# libre_oven_devkit.net
KiCad netlist of a schematic drawn in EasyEDA Pro
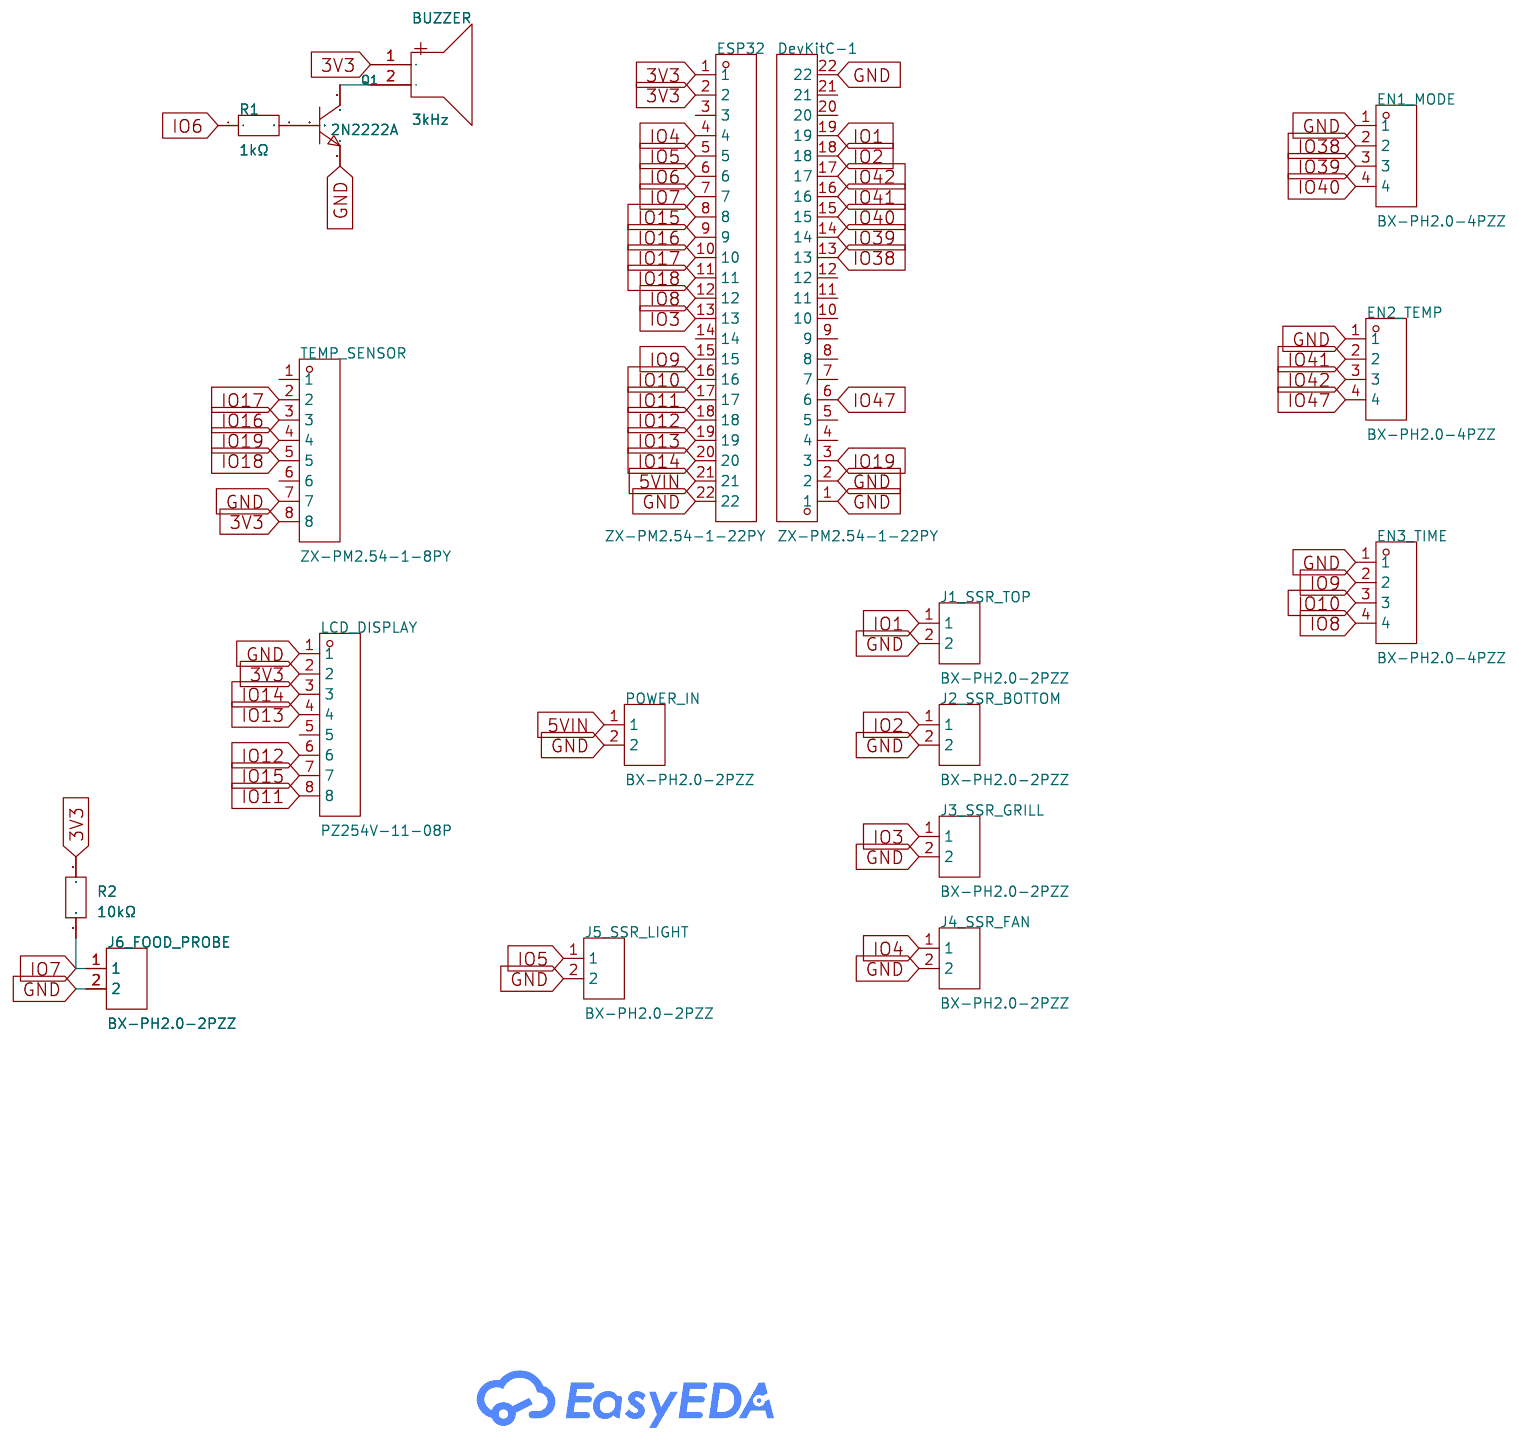
[diagram p0: schematic sheet]

(export (version "E")
  (design (tool "Eeschema 10.0.6"))
  (components
    (comp (ref "BUZZER")
      (value "3kHz")
      (footprint "easyedapro:BUZ-TH_BD9.0-P5.00-D0.6-FD")
      (fields (field (name "Manufacturer Part") "HNB09A03") (field (name "Manufacturer") "华能"))
      (libsource (lib "easyedapro") (part "HNB09A03"))
    )
    (comp (ref "DevKitC-1")
      (value "ZX-PM2.54-1-22PY")
      (footprint "easyedapro:HDR-TH_22P-P2.54-V-F")
      (fields (field (name "Manufacturer") "Megastar(兆星)"))
      (libsource (lib "easyedapro") (part "ZX-PM2.54-1-22PY"))
    )
    (comp (ref "EN1_MODE")
      (value "BX-PH2.0-4PZZ")
      (footprint "easyedapro:CONN-TH_4P-P2.00_BX-PH2.0-4PZZ")
      (fields (field (name "Manufacturer") "Bossie(博锡)"))
      (libsource (lib "easyedapro") (part "BX-PH2.0-4PZZ"))
    )
    (comp (ref "EN2_TEMP")
      (value "BX-PH2.0-4PZZ")
      (footprint "easyedapro:CONN-TH_4P-P2.00_BX-PH2.0-4PZZ")
      (fields (field (name "Manufacturer") "Bossie(博锡)"))
      (libsource (lib "easyedapro") (part "BX-PH2.0-4PZZ"))
    )
    (comp (ref "EN3_TIME")
      (value "BX-PH2.0-4PZZ")
      (footprint "easyedapro:CONN-TH_4P-P2.00_BX-PH2.0-4PZZ")
      (fields (field (name "Manufacturer") "Bossie(博锡)"))
      (libsource (lib "easyedapro") (part "BX-PH2.0-4PZZ"))
    )
    (comp (ref "ESP32")
      (value "ZX-PM2.54-1-22PY")
      (footprint "easyedapro:HDR-TH_22P-P2.54-V-F")
      (fields (field (name "Manufacturer") "Megastar(兆星)"))
      (libsource (lib "easyedapro") (part "ZX-PM2.54-1-22PY"))
    )
    (comp (ref "J1_SSR_TOP")
      (value "BX-PH2.0-2PZZ")
      (footprint "easyedapro:CONN-TH_2P-P2.00_BOSSIE_BX-PH2.0-2PZZ")
      (fields (field (name "Manufacturer") "Bossie(博锡)"))
      (libsource (lib "easyedapro") (part "BX-PH2.0-2PZZ"))
    )
    (comp (ref "J2_SSR_BOTTOM")
      (value "BX-PH2.0-2PZZ")
      (footprint "easyedapro:CONN-TH_2P-P2.00_BOSSIE_BX-PH2.0-2PZZ")
      (fields (field (name "Manufacturer") "Bossie(博锡)"))
      (libsource (lib "easyedapro") (part "BX-PH2.0-2PZZ"))
    )
    (comp (ref "J3_SSR_GRILL")
      (value "BX-PH2.0-2PZZ")
      (footprint "easyedapro:CONN-TH_2P-P2.00_BOSSIE_BX-PH2.0-2PZZ")
      (fields (field (name "Manufacturer") "Bossie(博锡)"))
      (libsource (lib "easyedapro") (part "BX-PH2.0-2PZZ"))
    )
    (comp (ref "J4_SSR_FAN")
      (value "BX-PH2.0-2PZZ")
      (footprint "easyedapro:CONN-TH_2P-P2.00_BOSSIE_BX-PH2.0-2PZZ")
      (fields (field (name "Manufacturer") "Bossie(博锡)"))
      (libsource (lib "easyedapro") (part "BX-PH2.0-2PZZ"))
    )
    (comp (ref "J5_SSR_LIGHT")
      (value "BX-PH2.0-2PZZ")
      (footprint "easyedapro:CONN-TH_2P-P2.00_BOSSIE_BX-PH2.0-2PZZ")
      (fields (field (name "Manufacturer") "Bossie(博锡)"))
      (libsource (lib "easyedapro") (part "BX-PH2.0-2PZZ"))
    )
    (comp (ref "J6_FOOD_PROBE")
      (value "BX-PH2.0-2PZZ")
      (footprint "easyedapro:CONN-TH_2P-P2.00_BOSSIE_BX-PH2.0-2PZZ")
      (fields (field (name "Manufacturer") "Bossie(博锡)"))
      (libsource (lib "easyedapro") (part "BX-PH2.0-2PZZ"))
    )
    (comp (ref "LCD_DISPLAY")
      (value "PZ254V-11-08P")
      (footprint "easyedapro:HDR-TH_8P-P2.54-V-M")
      (fields (field (name "Manufacturer") "XFCN(兴飞)"))
      (libsource (lib "easyedapro") (part "PZ254V-11-08P"))
    )
    (comp (ref "POWER_IN")
      (value "BX-PH2.0-2PZZ")
      (footprint "easyedapro:CONN-TH_2P-P2.00_BOSSIE_BX-PH2.0-2PZZ")
      (fields (field (name "Manufacturer") "Bossie(博锡)"))
      (libsource (lib "easyedapro") (part "BX-PH2.0-2PZZ"))
    )
    (comp (ref "Q1")
      (value "2N2222A")
      (footprint "easyedapro:TO-92-3_L4.9-W3.7-P1.27-L")
      (fields (field (name "Manufacturer") "ST(先科)"))
      (libsource (lib "easyedapro") (part "2N2222"))
    )
    (comp (ref "R1")
      (value "1kΩ")
      (footprint "easyedapro:RES-TH_BD2.7-L6.2-P10.20-D0.4")
      (fields (field (name "Manufacturer Part") "MF1/4W-1K±1%-ST52") (field (name "Manufacturer") "VO(翔胜)"))
      (libsource (lib "easyedapro") (part "MF1/4W-1K±1%-ST52"))
    )
    (comp (ref "R2")
      (value "10kΩ")
      (footprint "easyedapro:RES-TH_BD2.7-L6.2-P10.20-D0.4")
      (fields (field (name "Manufacturer Part") "MF1/4W-1K±1%-ST52") (field (name "Manufacturer") "VO(翔胜)"))
      (libsource (lib "easyedapro") (part "MF1/4W-1K±1%-ST52"))
    )
    (comp (ref "TEMP_SENSOR")
      (value "ZX-PM2.54-1-8PY")
      (footprint "easyedapro:HDR-TH_8P-P2.54-V-F")
      (fields (field (name "Manufacturer") "Megastar(兆星)"))
      (libsource (lib "easyedapro") (part "ZX-PM2.54-1-8PY"))
    )
  )
  (nets
    (net (code "1") (name "3V3") (class "Default")
      (node (ref "BUZZER") (pin "1") (pinfunction "+_1") (pintype "unspecified"))
      (node (ref "ESP32") (pin "1") (pinfunction "1_1") (pintype "unspecified"))
      (node (ref "ESP32") (pin "2") (pinfunction "2_2") (pintype "unspecified"))
      (node (ref "LCD_DISPLAY") (pin "2") (pinfunction "2_2") (pintype "unspecified"))
      (node (ref "R2") (pin "1") (pinfunction "1_1") (pintype "unspecified"))
      (node (ref "TEMP_SENSOR") (pin "8") (pinfunction "8_8") (pintype "unspecified"))
    )
    (net (code "2") (name "5VIN") (class "Default")
      (node (ref "ESP32") (pin "21") (pinfunction "21_21") (pintype "unspecified"))
      (node (ref "POWER_IN") (pin "1") (pinfunction "1_1") (pintype "unspecified"))
    )
    (net (code "3") (name "GND") (class "Default")
      (node (ref "DevKitC-1") (pin "1") (pinfunction "1_1") (pintype "unspecified"))
      (node (ref "DevKitC-1") (pin "2") (pinfunction "2_2") (pintype "unspecified"))
      (node (ref "DevKitC-1") (pin "22") (pinfunction "22_22") (pintype "unspecified"))
      (node (ref "EN1_MODE") (pin "1") (pinfunction "1_1") (pintype "unspecified"))
      (node (ref "EN2_TEMP") (pin "1") (pinfunction "1_1") (pintype "unspecified"))
      (node (ref "EN3_TIME") (pin "1") (pinfunction "1_1") (pintype "unspecified"))
      (node (ref "ESP32") (pin "22") (pinfunction "22_22") (pintype "unspecified"))
      (node (ref "J1_SSR_TOP") (pin "2") (pinfunction "2_2") (pintype "unspecified"))
      (node (ref "J2_SSR_BOTTOM") (pin "2") (pinfunction "2_2") (pintype "unspecified"))
      (node (ref "J3_SSR_GRILL") (pin "2") (pinfunction "2_2") (pintype "unspecified"))
      (node (ref "J4_SSR_FAN") (pin "2") (pinfunction "2_2") (pintype "unspecified"))
      (node (ref "J5_SSR_LIGHT") (pin "2") (pinfunction "2_2") (pintype "unspecified"))
      (node (ref "J6_FOOD_PROBE") (pin "2") (pinfunction "2_2") (pintype "unspecified"))
      (node (ref "LCD_DISPLAY") (pin "1") (pinfunction "1_1") (pintype "unspecified"))
      (node (ref "POWER_IN") (pin "2") (pinfunction "2_2") (pintype "unspecified"))
      (node (ref "Q1") (pin "1") (pinfunction "E_1") (pintype "input"))
      (node (ref "TEMP_SENSOR") (pin "7") (pinfunction "7_7") (pintype "unspecified"))
    )
    (net (code "4") (name "IO1") (class "Default")
      (node (ref "DevKitC-1") (pin "19") (pinfunction "19_19") (pintype "unspecified"))
      (node (ref "J1_SSR_TOP") (pin "1") (pinfunction "1_1") (pintype "unspecified"))
    )
    (net (code "5") (name "IO2") (class "Default")
      (node (ref "DevKitC-1") (pin "18") (pinfunction "18_18") (pintype "unspecified"))
      (node (ref "J2_SSR_BOTTOM") (pin "1") (pinfunction "1_1") (pintype "unspecified"))
    )
    (net (code "6") (name "IO3") (class "Default")
      (node (ref "ESP32") (pin "13") (pinfunction "13_13") (pintype "unspecified"))
      (node (ref "J3_SSR_GRILL") (pin "1") (pinfunction "1_1") (pintype "unspecified"))
    )
    (net (code "7") (name "IO4") (class "Default")
      (node (ref "ESP32") (pin "4") (pinfunction "4_4") (pintype "unspecified"))
      (node (ref "J4_SSR_FAN") (pin "1") (pinfunction "1_1") (pintype "unspecified"))
    )
    (net (code "8") (name "IO5") (class "Default")
      (node (ref "ESP32") (pin "5") (pinfunction "5_5") (pintype "unspecified"))
      (node (ref "J5_SSR_LIGHT") (pin "1") (pinfunction "1_1") (pintype "unspecified"))
    )
    (net (code "9") (name "IO6") (class "Default")
      (node (ref "ESP32") (pin "6") (pinfunction "6_6") (pintype "unspecified"))
      (node (ref "R1") (pin "1") (pinfunction "1_1") (pintype "unspecified"))
    )
    (net (code "10") (name "IO7") (class "Default")
      (node (ref "ESP32") (pin "7") (pinfunction "7_7") (pintype "unspecified"))
      (node (ref "J6_FOOD_PROBE") (pin "1") (pinfunction "1_1") (pintype "unspecified"))
      (node (ref "R2") (pin "2") (pinfunction "2_2") (pintype "unspecified"))
    )
    (net (code "11") (name "IO8") (class "Default")
      (node (ref "EN3_TIME") (pin "4") (pinfunction "4_4") (pintype "unspecified"))
      (node (ref "ESP32") (pin "12") (pinfunction "12_12") (pintype "unspecified"))
    )
    (net (code "12") (name "IO9") (class "Default")
      (node (ref "EN3_TIME") (pin "2") (pinfunction "2_2") (pintype "unspecified"))
      (node (ref "ESP32") (pin "15") (pinfunction "15_15") (pintype "unspecified"))
    )
    (net (code "13") (name "IO10") (class "Default")
      (node (ref "EN3_TIME") (pin "3") (pinfunction "3_3") (pintype "unspecified"))
      (node (ref "ESP32") (pin "16") (pinfunction "16_16") (pintype "unspecified"))
    )
    (net (code "14") (name "IO11") (class "Default")
      (node (ref "ESP32") (pin "17") (pinfunction "17_17") (pintype "unspecified"))
      (node (ref "LCD_DISPLAY") (pin "8") (pinfunction "8_8") (pintype "unspecified"))
    )
    (net (code "15") (name "IO12") (class "Default")
      (node (ref "ESP32") (pin "18") (pinfunction "18_18") (pintype "unspecified"))
      (node (ref "LCD_DISPLAY") (pin "6") (pinfunction "6_6") (pintype "unspecified"))
    )
    (net (code "16") (name "IO13") (class "Default")
      (node (ref "ESP32") (pin "19") (pinfunction "19_19") (pintype "unspecified"))
      (node (ref "LCD_DISPLAY") (pin "4") (pinfunction "4_4") (pintype "unspecified"))
    )
    (net (code "17") (name "IO14") (class "Default")
      (node (ref "ESP32") (pin "20") (pinfunction "20_20") (pintype "unspecified"))
      (node (ref "LCD_DISPLAY") (pin "3") (pinfunction "3_3") (pintype "unspecified"))
    )
    (net (code "18") (name "IO15") (class "Default")
      (node (ref "ESP32") (pin "8") (pinfunction "8_8") (pintype "unspecified"))
      (node (ref "LCD_DISPLAY") (pin "7") (pinfunction "7_7") (pintype "unspecified"))
    )
    (net (code "19") (name "IO16") (class "Default")
      (node (ref "ESP32") (pin "9") (pinfunction "9_9") (pintype "unspecified"))
      (node (ref "TEMP_SENSOR") (pin "3") (pinfunction "3_3") (pintype "unspecified"))
    )
    (net (code "20") (name "IO17") (class "Default")
      (node (ref "ESP32") (pin "10") (pinfunction "10_10") (pintype "unspecified"))
      (node (ref "TEMP_SENSOR") (pin "2") (pinfunction "2_2") (pintype "unspecified"))
    )
    (net (code "21") (name "IO18") (class "Default")
      (node (ref "ESP32") (pin "11") (pinfunction "11_11") (pintype "unspecified"))
      (node (ref "TEMP_SENSOR") (pin "5") (pinfunction "5_5") (pintype "unspecified"))
    )
    (net (code "22") (name "IO19") (class "Default")
      (node (ref "DevKitC-1") (pin "3") (pinfunction "3_3") (pintype "unspecified"))
      (node (ref "TEMP_SENSOR") (pin "4") (pinfunction "4_4") (pintype "unspecified"))
    )
    (net (code "23") (name "IO38") (class "Default")
      (node (ref "DevKitC-1") (pin "13") (pinfunction "13_13") (pintype "unspecified"))
      (node (ref "EN1_MODE") (pin "2") (pinfunction "2_2") (pintype "unspecified"))
    )
    (net (code "24") (name "IO39") (class "Default")
      (node (ref "DevKitC-1") (pin "14") (pinfunction "14_14") (pintype "unspecified"))
      (node (ref "EN1_MODE") (pin "3") (pinfunction "3_3") (pintype "unspecified"))
    )
    (net (code "25") (name "IO40") (class "Default")
      (node (ref "DevKitC-1") (pin "15") (pinfunction "15_15") (pintype "unspecified"))
      (node (ref "EN1_MODE") (pin "4") (pinfunction "4_4") (pintype "unspecified"))
    )
    (net (code "26") (name "IO41") (class "Default")
      (node (ref "DevKitC-1") (pin "16") (pinfunction "16_16") (pintype "unspecified"))
      (node (ref "EN2_TEMP") (pin "2") (pinfunction "2_2") (pintype "unspecified"))
    )
    (net (code "27") (name "IO42") (class "Default")
      (node (ref "DevKitC-1") (pin "17") (pinfunction "17_17") (pintype "unspecified"))
      (node (ref "EN2_TEMP") (pin "3") (pinfunction "3_3") (pintype "unspecified"))
    )
    (net (code "28") (name "IO47") (class "Default")
      (node (ref "DevKitC-1") (pin "6") (pinfunction "6_6") (pintype "unspecified"))
      (node (ref "EN2_TEMP") (pin "4") (pinfunction "4_4") (pintype "unspecified"))
    )
    (net (code "29") (name "Net-(BUZZER--)") (class "Default")
      (node (ref "BUZZER") (pin "2") (pinfunction "-_2") (pintype "unspecified"))
      (node (ref "Q1") (pin "3") (pinfunction "C_3") (pintype "input"))
    )
    (net (code "30") (name "Net-(Q1-B)") (class "Default")
      (node (ref "Q1") (pin "2") (pinfunction "B_2") (pintype "input"))
      (node (ref "R1") (pin "2") (pinfunction "2_2") (pintype "unspecified"))
    )
    (net (code "31") (name "unconnected-(DevKitC-1-Pad4)") (class "Default")
      (node (ref "DevKitC-1") (pin "4") (pinfunction "4_4") (pintype "unspecified"))
    )
    (net (code "32") (name "unconnected-(DevKitC-1-Pad5)") (class "Default")
      (node (ref "DevKitC-1") (pin "5") (pinfunction "5_5") (pintype "unspecified"))
    )
    (net (code "33") (name "unconnected-(DevKitC-1-Pad7)") (class "Default")
      (node (ref "DevKitC-1") (pin "7") (pinfunction "7_7") (pintype "unspecified"))
    )
    (net (code "34") (name "unconnected-(DevKitC-1-Pad8)") (class "Default")
      (node (ref "DevKitC-1") (pin "8") (pinfunction "8_8") (pintype "unspecified"))
    )
    (net (code "35") (name "unconnected-(DevKitC-1-Pad9)") (class "Default")
      (node (ref "DevKitC-1") (pin "9") (pinfunction "9_9") (pintype "unspecified"))
    )
    (net (code "36") (name "unconnected-(DevKitC-1-Pad10)") (class "Default")
      (node (ref "DevKitC-1") (pin "10") (pinfunction "10_10") (pintype "unspecified"))
    )
    (net (code "37") (name "unconnected-(DevKitC-1-Pad11)") (class "Default")
      (node (ref "DevKitC-1") (pin "11") (pinfunction "11_11") (pintype "unspecified"))
    )
    (net (code "38") (name "unconnected-(DevKitC-1-Pad12)") (class "Default")
      (node (ref "DevKitC-1") (pin "12") (pinfunction "12_12") (pintype "unspecified"))
    )
    (net (code "39") (name "unconnected-(DevKitC-1-Pad20)") (class "Default")
      (node (ref "DevKitC-1") (pin "20") (pinfunction "20_20") (pintype "unspecified"))
    )
    (net (code "40") (name "unconnected-(DevKitC-1-Pad21)") (class "Default")
      (node (ref "DevKitC-1") (pin "21") (pinfunction "21_21") (pintype "unspecified"))
    )
    (net (code "41") (name "unconnected-(ESP32-Pad3)") (class "Default")
      (node (ref "ESP32") (pin "3") (pinfunction "3_3") (pintype "unspecified"))
    )
    (net (code "42") (name "unconnected-(ESP32-Pad14)") (class "Default")
      (node (ref "ESP32") (pin "14") (pinfunction "14_14") (pintype "unspecified"))
    )
    (net (code "43") (name "unconnected-(LCD_DISPLAY-Pad5)") (class "Default")
      (node (ref "LCD_DISPLAY") (pin "5") (pinfunction "5_5") (pintype "unspecified"))
    )
    (net (code "44") (name "unconnected-(TEMP_SENSOR-Pad1)") (class "Default")
      (node (ref "TEMP_SENSOR") (pin "1") (pinfunction "1_1") (pintype "unspecified"))
    )
    (net (code "45") (name "unconnected-(TEMP_SENSOR-Pad6)") (class "Default")
      (node (ref "TEMP_SENSOR") (pin "6") (pinfunction "6_6") (pintype "unspecified"))
    )
  )
)
